# main.net
KiCad netlist of a schematic drawn in Altium Designer
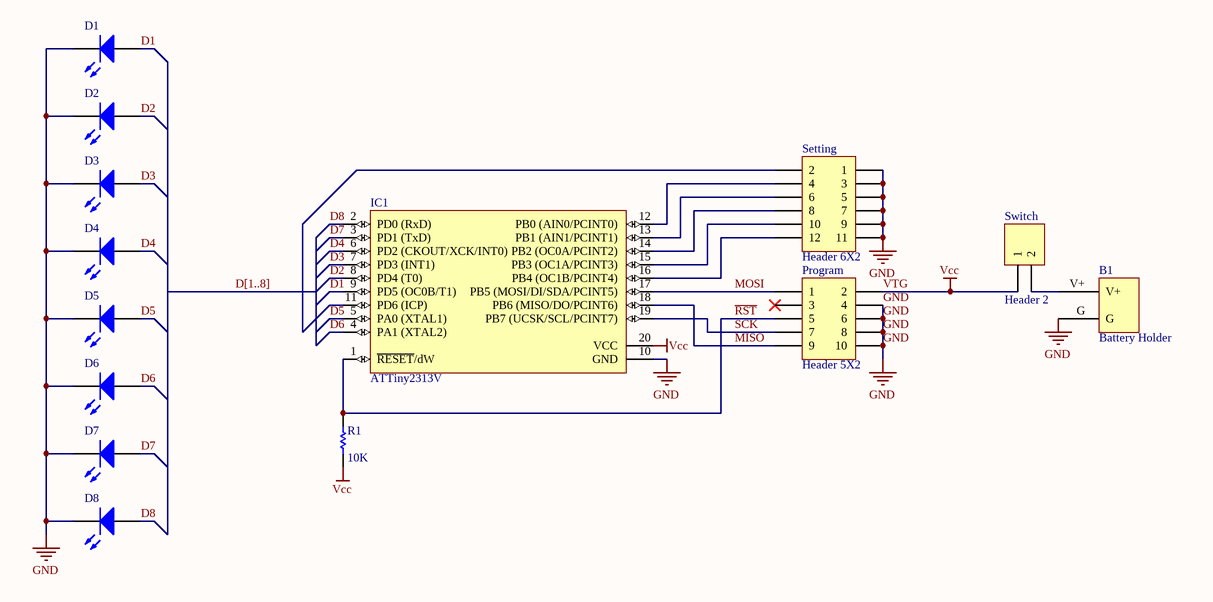
[diagram p0: main.SchDoc]

(export (version "E")
  (design (tool "Eeschema 10.0.6"))
  (components
    (comp (ref "B1")
      (value "Battery Holder")
      (footprint "Battery Holder")
      (libsource (lib "Connector") (part "Battery Holder"))
    )
    (comp (ref "D1")
      (value "LED1")
      (footprint "Led5mm")
      (description "Typical RED GaAs LED")
      (fields (field (name "PUBLISHER") "Altium Limited"))
      (libsource (lib "Miscellaneous Devices") (part "LED1"))
    )
    (comp (ref "D2")
      (value "LED1")
      (footprint "Led5mm")
      (description "Typical RED GaAs LED")
      (fields (field (name "PUBLISHER") "Altium Limited"))
      (libsource (lib "Miscellaneous Devices") (part "LED1"))
    )
    (comp (ref "D3")
      (value "LED1")
      (footprint "Led5mm")
      (description "Typical RED GaAs LED")
      (fields (field (name "PUBLISHER") "Altium Limited"))
      (libsource (lib "Miscellaneous Devices") (part "LED1"))
    )
    (comp (ref "D4")
      (value "LED1")
      (footprint "Led5mm")
      (description "Typical RED GaAs LED")
      (fields (field (name "PUBLISHER") "Altium Limited"))
      (libsource (lib "Miscellaneous Devices") (part "LED1"))
    )
    (comp (ref "D5")
      (value "LED1")
      (footprint "Led5mm")
      (description "Typical RED GaAs LED")
      (fields (field (name "PUBLISHER") "Altium Limited"))
      (libsource (lib "Miscellaneous Devices") (part "LED1"))
    )
    (comp (ref "D6")
      (value "LED1")
      (footprint "Led5mm")
      (description "Typical RED GaAs LED")
      (fields (field (name "PUBLISHER") "Altium Limited"))
      (libsource (lib "Miscellaneous Devices") (part "LED1"))
    )
    (comp (ref "D7")
      (value "LED1")
      (footprint "Led5mm")
      (description "Typical RED GaAs LED")
      (fields (field (name "PUBLISHER") "Altium Limited"))
      (libsource (lib "Miscellaneous Devices") (part "LED1"))
    )
    (comp (ref "D8")
      (value "LED1")
      (footprint "Led5mm")
      (description "Typical RED GaAs LED")
      (fields (field (name "PUBLISHER") "Altium Limited"))
      (libsource (lib "Miscellaneous Devices") (part "LED1"))
    )
    (comp (ref "IC1")
      (value "ATTiny2313V")
      (footprint "20P3")
      (description "8-Bit AVR Microcontroller with 2K Bytes of Flash Memory")
      (fields (field (name "PUBLISHER") "Altium Limited"))
      (libsource (lib "Atmel Microcontroller 8-Bit AVR") (part "ATtiny2313V-PI"))
    )
    (comp (ref "Program")
      (value "Header 5X2")
      (footprint "Box2x5")
      (description "Header, 5-Pin, Dual row")
      (fields (field (name "PUBLISHER") "Altium Limited"))
      (libsource (lib "Miscellaneous Connectors") (part "Header 5X2"))
    )
    (comp (ref "R1")
      (value "10K")
      (footprint "AXIAL-0.3")
      (description "Resistor")
      (fields (field (name "Comment") "Res1") (field (name "PUBLISHER") "Altium Limited"))
      (libsource (lib "Miscellaneous Devices") (part "Res1"))
    )
    (comp (ref "Setting")
      (value "Header 6X2")
      (footprint "HDR2X6")
      (description "Header, 6-Pin, Dual row")
      (fields (field (name "PUBLISHER") "Altium Limited"))
      (libsource (lib "Miscellaneous Connectors") (part "Header 6X2"))
    )
    (comp (ref "Switch")
      (value "Header 2")
      (footprint "HDR1X2")
      (description "Header, 2-Pin")
      (fields (field (name "PUBLISHER") "Altium Limited"))
      (libsource (lib "Miscellaneous Connectors") (part "Header 2"))
    )
  )
  (nets
    (net (code "1") (name "/D1") (class "Default")
      (node (ref "D1") (pin "1") (pinfunction "A_1") (pintype "passive"))
      (node (ref "IC1") (pin "9") (pinfunction "PD5_(OC0B/T1)_9") (pintype "bidirectional"))
    )
    (net (code "2") (name "/D2") (class "Default")
      (node (ref "D2") (pin "1") (pinfunction "A_1") (pintype "passive"))
      (node (ref "IC1") (pin "8") (pinfunction "PD4_(T0)_8") (pintype "bidirectional"))
    )
    (net (code "3") (name "/D3") (class "Default")
      (node (ref "D3") (pin "1") (pinfunction "A_1") (pintype "passive"))
      (node (ref "IC1") (pin "7") (pinfunction "PD3_(INT1)_7") (pintype "bidirectional"))
    )
    (net (code "4") (name "/D4") (class "Default")
      (node (ref "D4") (pin "1") (pinfunction "A_1") (pintype "passive"))
      (node (ref "IC1") (pin "6") (pinfunction "PD2_(CKOUT/XCK/INT0)_6") (pintype "bidirectional"))
    )
    (net (code "5") (name "/D5") (class "Default")
      (node (ref "D5") (pin "1") (pinfunction "A_1") (pintype "passive"))
      (node (ref "IC1") (pin "5") (pinfunction "PA0_(XTAL1)_5") (pintype "bidirectional"))
    )
    (net (code "6") (name "/D6") (class "Default")
      (node (ref "D6") (pin "1") (pinfunction "A_1") (pintype "passive"))
      (node (ref "IC1") (pin "4") (pinfunction "PA1_(XTAL2)_4") (pintype "bidirectional"))
    )
    (net (code "7") (name "/D7") (class "Default")
      (node (ref "D7") (pin "1") (pinfunction "A_1") (pintype "passive"))
      (node (ref "IC1") (pin "3") (pinfunction "PD1_(TxD)_3") (pintype "bidirectional"))
    )
    (net (code "8") (name "/D8") (class "Default")
      (node (ref "D8") (pin "1") (pinfunction "A_1") (pintype "passive"))
      (node (ref "IC1") (pin "2") (pinfunction "PD0_(RxD)_2") (pintype "bidirectional"))
    )
    (net (code "10") (name "/MISO") (class "Default")
      (node (ref "IC1") (pin "18") (pinfunction "PB6_(MISO/DO/PCINT6)_18") (pintype "bidirectional"))
      (node (ref "Program") (pin "9") (pinfunction "9_9") (pintype "passive"))
    )
    (net (code "11") (name "/MOSI") (class "Default")
      (node (ref "IC1") (pin "17") (pinfunction "PB5_(MOSI/DI/SDA/PCINT5)_17") (pintype "bidirectional"))
      (node (ref "Program") (pin "1") (pinfunction "1_1") (pintype "passive"))
    )
    (net (code "12") (name "/SCK") (class "Default")
      (node (ref "IC1") (pin "19") (pinfunction "PB7_(UCSK/SCL/PCINT7)_19") (pintype "bidirectional"))
      (node (ref "Program") (pin "7") (pinfunction "7_7") (pintype "passive"))
    )
    (net (code "13") (name "/~{RST}") (class "Default")
      (node (ref "IC1") (pin "1") (pinfunction "~{RESET}/dW_1") (pintype "bidirectional"))
      (node (ref "Program") (pin "5") (pinfunction "5_5") (pintype "passive"))
      (node (ref "R1") (pin "2") (pinfunction "2_2") (pintype "passive"))
    )
    (net (code "14") (name "GND") (class "Default")
      (node (ref "B1") (pin "G") (pinfunction "G_G") (pintype "power_in"))
      (node (ref "D1") (pin "2") (pinfunction "K_2") (pintype "passive"))
      (node (ref "D2") (pin "2") (pinfunction "K_2") (pintype "passive"))
      (node (ref "D3") (pin "2") (pinfunction "K_2") (pintype "passive"))
      (node (ref "D4") (pin "2") (pinfunction "K_2") (pintype "passive"))
      (node (ref "D5") (pin "2") (pinfunction "K_2") (pintype "passive"))
      (node (ref "D6") (pin "2") (pinfunction "K_2") (pintype "passive"))
      (node (ref "D7") (pin "2") (pinfunction "K_2") (pintype "passive"))
      (node (ref "D8") (pin "2") (pinfunction "K_2") (pintype "passive"))
      (node (ref "IC1") (pin "10") (pinfunction "GND_10") (pintype "power_in"))
      (node (ref "Program") (pin "10") (pinfunction "10_10") (pintype "passive"))
      (node (ref "Program") (pin "4") (pinfunction "4_4") (pintype "passive"))
      (node (ref "Program") (pin "6") (pinfunction "6_6") (pintype "passive"))
      (node (ref "Program") (pin "8") (pinfunction "8_8") (pintype "passive"))
      (node (ref "Setting") (pin "1") (pinfunction "1_1") (pintype "passive"))
      (node (ref "Setting") (pin "11") (pinfunction "11_11") (pintype "passive"))
      (node (ref "Setting") (pin "3") (pinfunction "3_3") (pintype "passive"))
      (node (ref "Setting") (pin "5") (pinfunction "5_5") (pintype "passive"))
      (node (ref "Setting") (pin "7") (pinfunction "7_7") (pintype "passive"))
      (node (ref "Setting") (pin "9") (pinfunction "9_9") (pintype "passive"))
    )
    (net (code "15") (name "Net-(B1-PadV+)") (class "Default")
      (node (ref "B1") (pin "V+") (pinfunction "V+_V+") (pintype "power_in"))
      (node (ref "Switch") (pin "2") (pinfunction "2_2") (pintype "passive"))
    )
    (net (code "16") (name "Net-(IC1-PB0_(AIN0{slash}PCINT0))") (class "Default")
      (node (ref "IC1") (pin "12") (pinfunction "PB0_(AIN0/PCINT0)_12") (pintype "bidirectional"))
      (node (ref "Setting") (pin "4") (pinfunction "4_4") (pintype "passive"))
    )
    (net (code "17") (name "Net-(IC1-PB1_(AIN1{slash}PCINT1))") (class "Default")
      (node (ref "IC1") (pin "13") (pinfunction "PB1_(AIN1/PCINT1)_13") (pintype "bidirectional"))
      (node (ref "Setting") (pin "6") (pinfunction "6_6") (pintype "passive"))
    )
    (net (code "18") (name "Net-(IC1-PB2_(OC0A{slash}PCINT2))") (class "Default")
      (node (ref "IC1") (pin "14") (pinfunction "PB2_(OC0A/PCINT2)_14") (pintype "bidirectional"))
      (node (ref "Setting") (pin "8") (pinfunction "8_8") (pintype "passive"))
    )
    (net (code "19") (name "Net-(IC1-PB3_(OC1A{slash}PCINT3))") (class "Default")
      (node (ref "IC1") (pin "15") (pinfunction "PB3_(OC1A/PCINT3)_15") (pintype "bidirectional"))
      (node (ref "Setting") (pin "10") (pinfunction "10_10") (pintype "passive"))
    )
    (net (code "20") (name "Net-(IC1-PB4_(OC1B{slash}PCINT4))") (class "Default")
      (node (ref "IC1") (pin "16") (pinfunction "PB4_(OC1B/PCINT4)_16") (pintype "bidirectional"))
      (node (ref "Setting") (pin "12") (pinfunction "12_12") (pintype "passive"))
    )
    (net (code "21") (name "Net-(IC1-PD6_(ICP))") (class "Default")
      (node (ref "IC1") (pin "11") (pinfunction "PD6_(ICP)_11") (pintype "bidirectional"))
      (node (ref "Setting") (pin "2") (pinfunction "2_2") (pintype "passive"))
    )
    (net (code "22") (name "Vcc") (class "Default")
      (node (ref "IC1") (pin "20") (pinfunction "VCC_20") (pintype "power_in"))
      (node (ref "Program") (pin "2") (pinfunction "2_2") (pintype "passive"))
      (node (ref "R1") (pin "1") (pinfunction "1_1") (pintype "passive"))
      (node (ref "Switch") (pin "1") (pinfunction "1_1") (pintype "passive"))
    )
    (net (code "23") (name "unconnected-(Program-Pad3)") (class "Default")
      (node (ref "Program") (pin "3") (pinfunction "3_3") (pintype "passive+no_connect"))
    )
  )
)
